# PIC_Uhrfinal.net
KiCad netlist of a schematic drawn in EAGLE
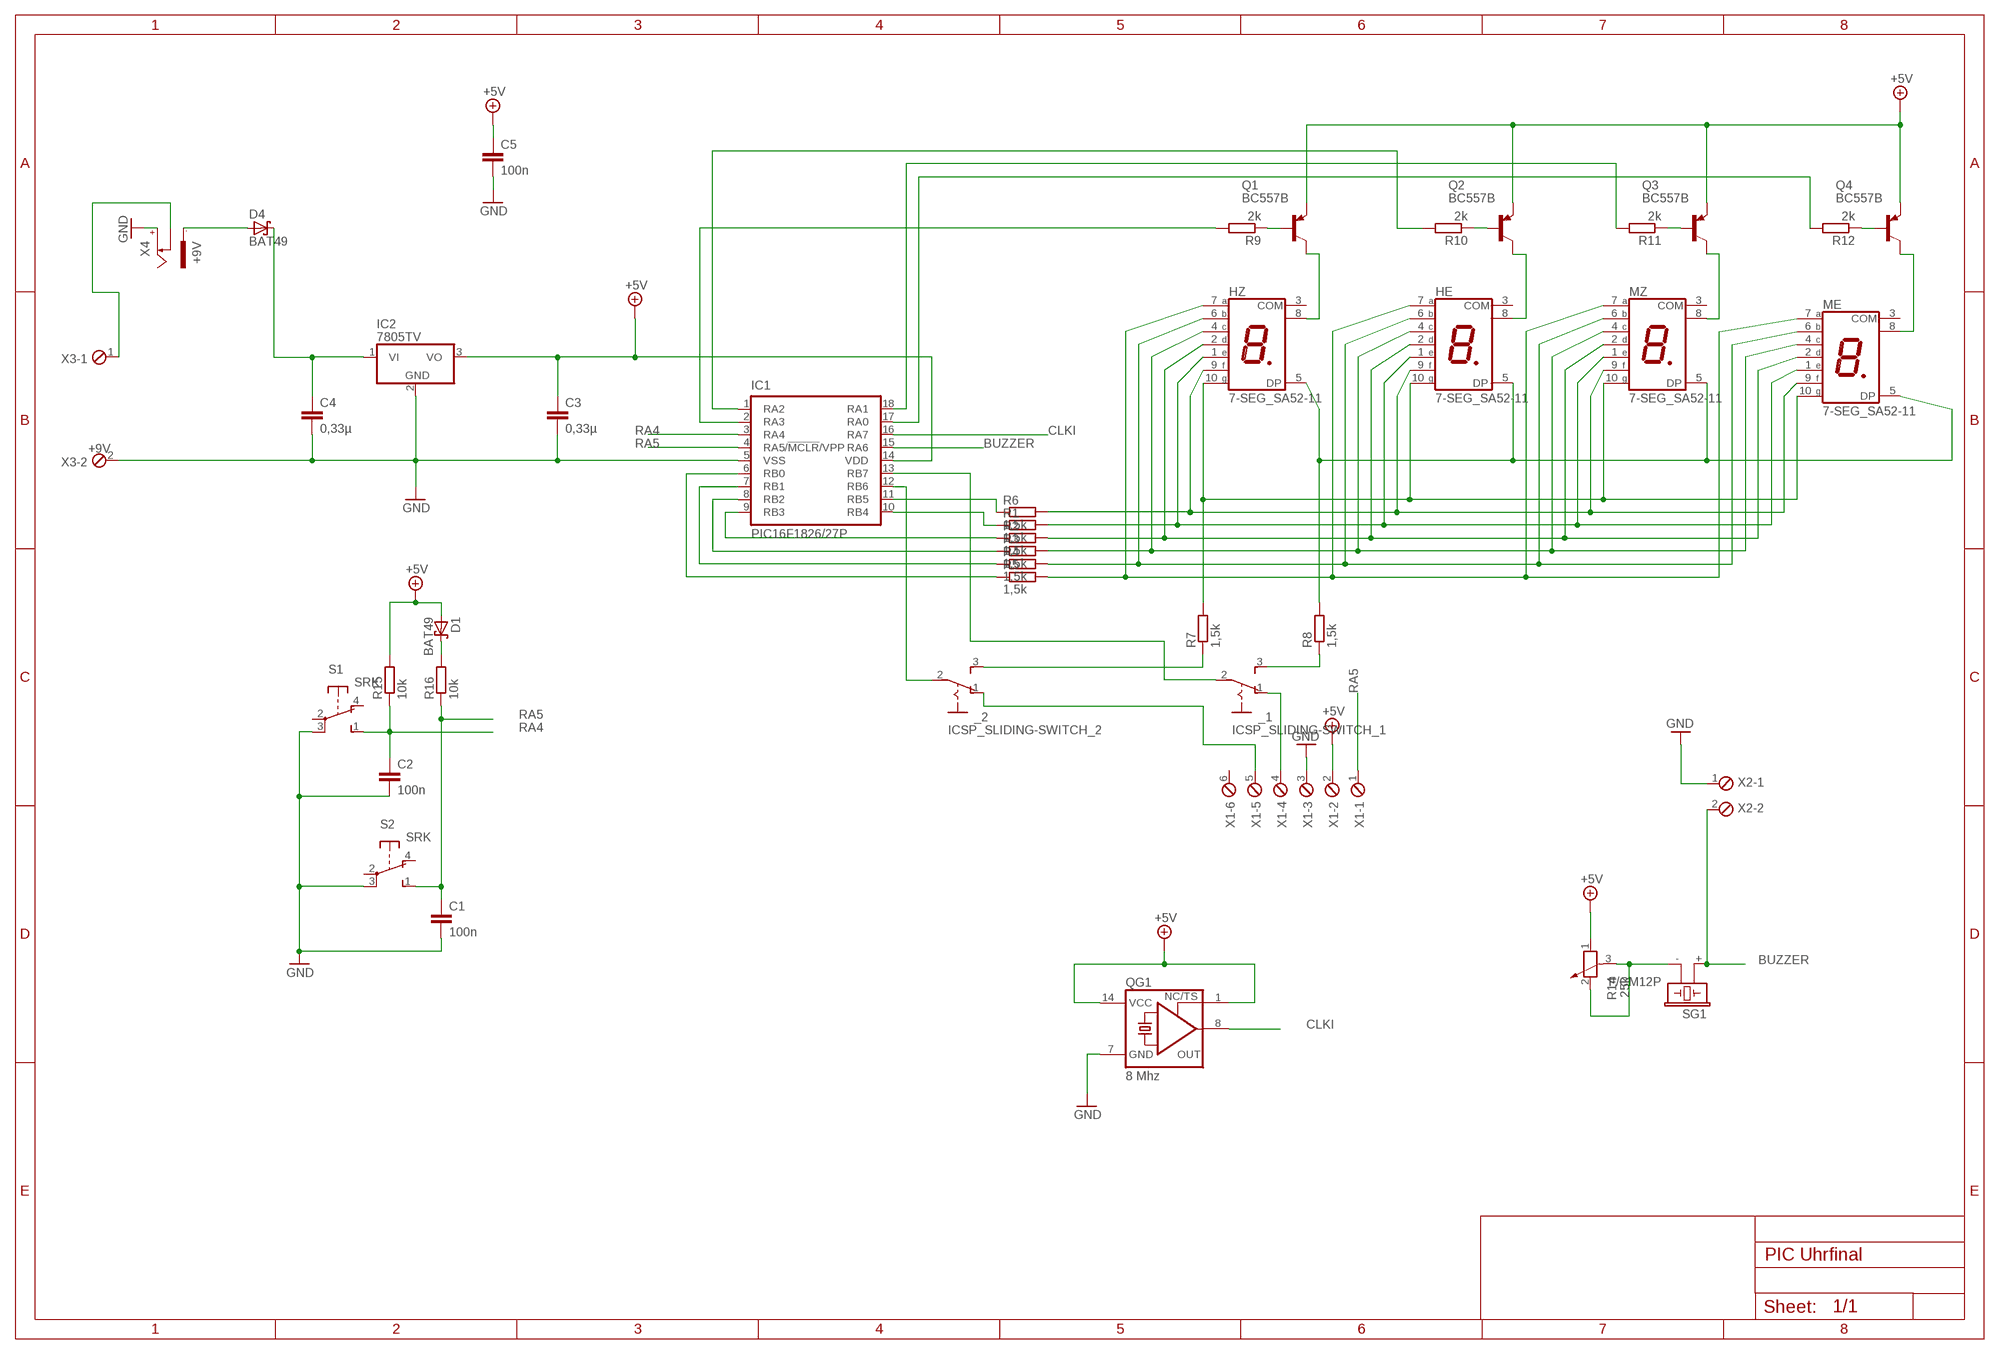
[diagram p0: schematic, sheet 1]

(export (version "E")
  (design (tool "Eeschema 10.0.6"))
  (components
    (comp (ref "C1")
      (value "100n")
      (footprint "eagle-import:C1206")
      (libsource (lib "eagle-import") (part "C-EUC1206"))
    )
    (comp (ref "C2")
      (value "100n")
      (footprint "eagle-import:C1206")
      (libsource (lib "eagle-import") (part "C-EUC1206"))
    )
    (comp (ref "C3")
      (value "0,33µ")
      (footprint "eagle-import:C1206")
      (libsource (lib "eagle-import") (part "C-EUC1206"))
    )
    (comp (ref "C4")
      (value "0,33µ")
      (footprint "eagle-import:C1206")
      (libsource (lib "eagle-import") (part "C-EUC1206"))
    )
    (comp (ref "C5")
      (value "100n")
      (footprint "eagle-import:C1206")
      (libsource (lib "eagle-import") (part "C-EUC1206"))
    )
    (comp (ref "D1")
      (value "BAT49")
      (footprint "eagle-import:DO41-10")
      (libsource (lib "eagle-import") (part "BAT49"))
    )
    (comp (ref "D4")
      (value "BAT49")
      (footprint "eagle-import:DO41-10")
      (libsource (lib "eagle-import") (part "BAT49"))
    )
    (comp (ref "HE")
      (value "7-SEG_SA52-11")
      (footprint "eagle-import:SA52-11")
      (libsource (lib "eagle-import") (part "7-SEG_SA52-11"))
    )
    (comp (ref "HZ")
      (value "7-SEG_SA52-11")
      (footprint "eagle-import:SA52-11")
      (libsource (lib "eagle-import") (part "7-SEG_SA52-11"))
    )
    (comp (ref "IC1")
      (value "PIC16F1826/27P")
      (footprint "eagle-import:DIL18")
      (libsource (lib "eagle-import") (part "PIC16F1826/27P"))
    )
    (comp (ref "IC2")
      (value "7805TV")
      (footprint "eagle-import:TO220V")
      (libsource (lib "eagle-import") (part "78TV05"))
    )
    (comp (ref "ICSP_SLIDING-SWITCH_1")
      (value "_1")
      (footprint "eagle-import:M251")
      (libsource (lib "eagle-import") (part "M251"))
    )
    (comp (ref "ICSP_SLIDING-SWITCH_2")
      (value "_2")
      (footprint "eagle-import:M251")
      (libsource (lib "eagle-import") (part "M251"))
    )
    (comp (ref "ME")
      (value "7-SEG_SA52-11")
      (footprint "eagle-import:SA52-11")
      (libsource (lib "eagle-import") (part "7-SEG_SA52-11"))
    )
    (comp (ref "MZ")
      (value "7-SEG_SA52-11")
      (footprint "eagle-import:SA52-11")
      (libsource (lib "eagle-import") (part "7-SEG_SA52-11"))
    )
    (comp (ref "Q1")
      (value "BC557B")
      (footprint "eagle-import:TO92-EBC")
      (libsource (lib "eagle-import") (part "BC557B"))
    )
    (comp (ref "Q2")
      (value "BC557B")
      (footprint "eagle-import:TO92-EBC")
      (libsource (lib "eagle-import") (part "BC557B"))
    )
    (comp (ref "Q3")
      (value "BC557B")
      (footprint "eagle-import:TO92-EBC")
      (libsource (lib "eagle-import") (part "BC557B"))
    )
    (comp (ref "Q4")
      (value "BC557B")
      (footprint "eagle-import:TO92-EBC")
      (libsource (lib "eagle-import") (part "BC557B"))
    )
    (comp (ref "QG1")
      (value "8 Mhz")
      (footprint "eagle-import:DIL14S")
      (libsource (lib "eagle-import") (part "XO-14"))
    )
    (comp (ref "R1")
      (value "1,5k")
      (footprint "eagle-import:R0805W")
      (libsource (lib "eagle-import") (part "R-EU_R0805W"))
    )
    (comp (ref "R2")
      (value "1,5k")
      (footprint "eagle-import:R0805W")
      (libsource (lib "eagle-import") (part "R-EU_R0805W"))
    )
    (comp (ref "R3")
      (value "1,5k")
      (footprint "eagle-import:R0805W")
      (libsource (lib "eagle-import") (part "R-EU_R0805W"))
    )
    (comp (ref "R4")
      (value "1,5k")
      (footprint "eagle-import:R0805W")
      (libsource (lib "eagle-import") (part "R-EU_R0805W"))
    )
    (comp (ref "R5")
      (value "1,5k")
      (footprint "eagle-import:R0805W")
      (libsource (lib "eagle-import") (part "R-EU_R0805W"))
    )
    (comp (ref "R6")
      (value "1,5k")
      (footprint "eagle-import:R0805W")
      (libsource (lib "eagle-import") (part "R-EU_R0805W"))
    )
    (comp (ref "R7")
      (value "1,5k")
      (footprint "eagle-import:R0805W")
      (libsource (lib "eagle-import") (part "R-EU_R0805W"))
    )
    (comp (ref "R8")
      (value "1,5k")
      (footprint "eagle-import:R0805W")
      (libsource (lib "eagle-import") (part "R-EU_R0805W"))
    )
    (comp (ref "R9")
      (value "2k")
      (footprint "eagle-import:R0805W")
      (libsource (lib "eagle-import") (part "R-EU_R0805W"))
    )
    (comp (ref "R10")
      (value "2k")
      (footprint "eagle-import:R0805W")
      (libsource (lib "eagle-import") (part "R-EU_R0805W"))
    )
    (comp (ref "R11")
      (value "2k")
      (footprint "eagle-import:R0805W")
      (libsource (lib "eagle-import") (part "R-EU_R0805W"))
    )
    (comp (ref "R12")
      (value "2k")
      (footprint "eagle-import:R0805W")
      (libsource (lib "eagle-import") (part "R-EU_R0805W"))
    )
    (comp (ref "R14")
      (value "25k")
      (footprint "eagle-import:PT-10")
      (libsource (lib "eagle-import") (part "POTENTIOMETER_PT-10"))
    )
    (comp (ref "R15")
      (value "10k")
      (footprint "eagle-import:R1206")
      (libsource (lib "eagle-import") (part "R-EU_R1206"))
    )
    (comp (ref "R16")
      (value "10k")
      (footprint "eagle-import:R1206")
      (libsource (lib "eagle-import") (part "R-EU_R1206"))
    )
    (comp (ref "S1")
      (value "SRK")
      (footprint "eagle-import:SRK")
      (libsource (lib "eagle-import") (part "SRK"))
    )
    (comp (ref "S2")
      (value "SRK")
      (footprint "eagle-import:SRK")
      (libsource (lib "eagle-import") (part "SRK"))
    )
    (comp (ref "SG1")
      (value "F/CM12P")
      (footprint "eagle-import:F_CM12P")
      (libsource (lib "eagle-import") (part "F/CM12P"))
    )
    (comp (ref "X1")
      (value "MPT6")
      (footprint "eagle-import:6POL254")
      (libsource (lib "eagle-import") (part "MPT6"))
    )
    (comp (ref "X2")
      (value "MPT2")
      (footprint "eagle-import:2POL254")
      (libsource (lib "eagle-import") (part "MPT2"))
    )
    (comp (ref "X3")
      (value "+9V")
      (footprint "eagle-import:2POL254")
      (libsource (lib "eagle-import") (part "MPT2"))
    )
    (comp (ref "X4")
      (value "+9V")
      (footprint "eagle-import:737992-5")
      (libsource (lib "eagle-import") (part "737992-55"))
    )
  )
  (nets
    (net (code "1") (name "+5V") (class "Default")
      (node (ref "C3") (pin "1") (pinfunction "1_1") (pintype "passive"))
      (node (ref "C5") (pin "1") (pinfunction "1_1") (pintype "passive"))
      (node (ref "D1") (pin "A") (pinfunction "A_A") (pintype "passive"))
      (node (ref "IC1") (pin "14") (pinfunction "VDD_14") (pintype "power_in"))
      (node (ref "IC2") (pin "3") (pinfunction "VO_3") (pintype "passive"))
      (node (ref "Q1") (pin "E") (pinfunction "E_E") (pintype "passive"))
      (node (ref "Q2") (pin "E") (pinfunction "E_E") (pintype "passive"))
      (node (ref "Q3") (pin "E") (pinfunction "E_E") (pintype "passive"))
      (node (ref "Q4") (pin "E") (pinfunction "E_E") (pintype "passive"))
      (node (ref "QG1") (pin "1") (pinfunction "TS_1") (pintype "passive"))
      (node (ref "QG1") (pin "14") (pinfunction "VCC_14") (pintype "power_in"))
      (node (ref "R14") (pin "1") (pinfunction "1_1") (pintype "passive"))
      (node (ref "R15") (pin "2") (pinfunction "2_2") (pintype "passive"))
      (node (ref "X1") (pin "2") (pinfunction "1_2") (pintype "passive"))
    )
    (net (code "2") (name "/BUZZER") (class "Default")
      (node (ref "IC1") (pin "15") (pinfunction "RA6_15") (pintype "bidirectional"))
      (node (ref "SG1") (pin "+") (pinfunction "1_+") (pintype "passive"))
      (node (ref "X2") (pin "2") (pinfunction "1_2") (pintype "passive"))
    )
    (net (code "3") (name "/CLKI") (class "Default")
      (node (ref "IC1") (pin "16") (pinfunction "RA7_16") (pintype "bidirectional"))
      (node (ref "QG1") (pin "8") (pinfunction "OUT_8") (pintype "output"))
    )
    (net (code "4") (name "/RA4") (class "Default")
      (node (ref "C2") (pin "1") (pinfunction "1_1") (pintype "passive"))
      (node (ref "IC1") (pin "3") (pinfunction "RA4_3") (pintype "bidirectional"))
      (node (ref "R15") (pin "1") (pinfunction "1_1") (pintype "passive"))
      (node (ref "S1") (pin "1") (pinfunction "S_1") (pintype "passive"))
    )
    (net (code "5") (name "/RA5") (class "Default")
      (node (ref "C1") (pin "1") (pinfunction "1_1") (pintype "passive"))
      (node (ref "IC1") (pin "4") (pinfunction "RA5/~{MCLR}/VPP_4") (pintype "bidirectional"))
      (node (ref "R16") (pin "1") (pinfunction "1_1") (pintype "passive"))
      (node (ref "S2") (pin "1") (pinfunction "S_1") (pintype "passive"))
      (node (ref "X1") (pin "1") (pinfunction "1_1") (pintype "passive"))
    )
    (net (code "6") (name "GND") (class "Default")
      (node (ref "C1") (pin "2") (pinfunction "2_2") (pintype "passive"))
      (node (ref "C2") (pin "2") (pinfunction "2_2") (pintype "passive"))
      (node (ref "C3") (pin "2") (pinfunction "2_2") (pintype "passive"))
      (node (ref "C4") (pin "2") (pinfunction "2_2") (pintype "passive"))
      (node (ref "C5") (pin "2") (pinfunction "2_2") (pintype "passive"))
      (node (ref "IC1") (pin "5") (pinfunction "VSS_5") (pintype "power_in"))
      (node (ref "IC2") (pin "2") (pinfunction "GND_2") (pintype "passive"))
      (node (ref "QG1") (pin "7") (pinfunction "GND_7") (pintype "power_in"))
      (node (ref "S1") (pin "3") (pinfunction "P_3") (pintype "passive"))
      (node (ref "S2") (pin "3") (pinfunction "P_3") (pintype "passive"))
      (node (ref "X1") (pin "3") (pinfunction "1_3") (pintype "passive"))
      (node (ref "X2") (pin "1") (pinfunction "1_1") (pintype "passive"))
      (node (ref "X3") (pin "2") (pinfunction "1_2") (pintype "passive"))
      (node (ref "X4") (pin "+") (pinfunction "+_+") (pintype "passive"))
    )
    (net (code "7") (name "Net-(D1-PadC)") (class "Default")
      (node (ref "D1") (pin "C") (pinfunction "C_C") (pintype "passive"))
      (node (ref "R16") (pin "2") (pinfunction "2_2") (pintype "passive"))
    )
    (net (code "8") (name "Net-(D4-PadA)") (class "Default")
      (node (ref "D4") (pin "A") (pinfunction "A_A") (pintype "passive"))
      (node (ref "X4") (pin "-1") (pinfunction "-1_-1") (pintype "passive"))
    )
    (net (code "9") (name "Net-(HE-A)") (class "Default")
      (node (ref "HE") (pin "7") (pinfunction "A_7") (pintype "passive"))
      (node (ref "HZ") (pin "7") (pinfunction "A_7") (pintype "passive"))
      (node (ref "ME") (pin "7") (pinfunction "A_7") (pintype "passive"))
      (node (ref "MZ") (pin "7") (pinfunction "A_7") (pintype "passive"))
      (node (ref "R5") (pin "2") (pinfunction "2_2") (pintype "passive"))
    )
    (net (code "10") (name "Net-(HE-B)") (class "Default")
      (node (ref "HE") (pin "6") (pinfunction "B_6") (pintype "passive"))
      (node (ref "HZ") (pin "6") (pinfunction "B_6") (pintype "passive"))
      (node (ref "ME") (pin "6") (pinfunction "B_6") (pintype "passive"))
      (node (ref "MZ") (pin "6") (pinfunction "B_6") (pintype "passive"))
      (node (ref "R4") (pin "2") (pinfunction "2_2") (pintype "passive"))
    )
    (net (code "11") (name "Net-(HE-C)") (class "Default")
      (node (ref "HE") (pin "4") (pinfunction "C_4") (pintype "passive"))
      (node (ref "HZ") (pin "4") (pinfunction "C_4") (pintype "passive"))
      (node (ref "ME") (pin "4") (pinfunction "C_4") (pintype "passive"))
      (node (ref "MZ") (pin "4") (pinfunction "C_4") (pintype "passive"))
      (node (ref "R3") (pin "2") (pinfunction "2_2") (pintype "passive"))
    )
    (net (code "12") (name "Net-(HE-COM-Pad8)") (class "Default")
      (node (ref "HE") (pin "8") (pinfunction "COM_8") (pintype "passive"))
      (node (ref "Q2") (pin "C") (pinfunction "C_C") (pintype "passive"))
    )
    (net (code "13") (name "Net-(HE-D)") (class "Default")
      (node (ref "HE") (pin "2") (pinfunction "D_2") (pintype "passive"))
      (node (ref "HZ") (pin "2") (pinfunction "D_2") (pintype "passive"))
      (node (ref "ME") (pin "2") (pinfunction "D_2") (pintype "passive"))
      (node (ref "MZ") (pin "2") (pinfunction "D_2") (pintype "passive"))
      (node (ref "R2") (pin "2") (pinfunction "2_2") (pintype "passive"))
    )
    (net (code "14") (name "Net-(HE-DP)") (class "Default")
      (node (ref "HE") (pin "5") (pinfunction "DP_5") (pintype "passive"))
      (node (ref "HZ") (pin "5") (pinfunction "DP_5") (pintype "passive"))
      (node (ref "ME") (pin "5") (pinfunction "DP_5") (pintype "passive"))
      (node (ref "MZ") (pin "5") (pinfunction "DP_5") (pintype "passive"))
      (node (ref "R8") (pin "2") (pinfunction "2_2") (pintype "passive"))
    )
    (net (code "15") (name "Net-(HE-E)") (class "Default")
      (node (ref "HE") (pin "1") (pinfunction "E_1") (pintype "passive"))
      (node (ref "HZ") (pin "1") (pinfunction "E_1") (pintype "passive"))
      (node (ref "ME") (pin "1") (pinfunction "E_1") (pintype "passive"))
      (node (ref "MZ") (pin "1") (pinfunction "E_1") (pintype "passive"))
      (node (ref "R1") (pin "2") (pinfunction "2_2") (pintype "passive"))
    )
    (net (code "16") (name "Net-(HE-F)") (class "Default")
      (node (ref "HE") (pin "9") (pinfunction "F_9") (pintype "passive"))
      (node (ref "HZ") (pin "9") (pinfunction "F_9") (pintype "passive"))
      (node (ref "ME") (pin "9") (pinfunction "F_9") (pintype "passive"))
      (node (ref "MZ") (pin "9") (pinfunction "F_9") (pintype "passive"))
      (node (ref "R6") (pin "2") (pinfunction "2_2") (pintype "passive"))
    )
    (net (code "17") (name "Net-(HE-G)") (class "Default")
      (node (ref "HE") (pin "10") (pinfunction "G_10") (pintype "passive"))
      (node (ref "HZ") (pin "10") (pinfunction "G_10") (pintype "passive"))
      (node (ref "ME") (pin "10") (pinfunction "G_10") (pintype "passive"))
      (node (ref "MZ") (pin "10") (pinfunction "G_10") (pintype "passive"))
      (node (ref "R7") (pin "2") (pinfunction "2_2") (pintype "passive"))
    )
    (net (code "18") (name "Net-(HZ-COM-Pad8)") (class "Default")
      (node (ref "HZ") (pin "8") (pinfunction "COM_8") (pintype "passive"))
      (node (ref "Q1") (pin "C") (pinfunction "C_C") (pintype "passive"))
    )
    (net (code "19") (name "Net-(IC1-RA0)") (class "Default")
      (node (ref "IC1") (pin "17") (pinfunction "RA0_17") (pintype "bidirectional"))
      (node (ref "R12") (pin "2") (pinfunction "2_2") (pintype "passive"))
    )
    (net (code "20") (name "Net-(IC1-RA1)") (class "Default")
      (node (ref "IC1") (pin "18") (pinfunction "RA1_18") (pintype "bidirectional"))
      (node (ref "R11") (pin "2") (pinfunction "2_2") (pintype "passive"))
    )
    (net (code "21") (name "Net-(IC1-RA2)") (class "Default")
      (node (ref "IC1") (pin "1") (pinfunction "RA2_1") (pintype "bidirectional"))
      (node (ref "R10") (pin "2") (pinfunction "2_2") (pintype "passive"))
    )
    (net (code "22") (name "Net-(IC1-RA3)") (class "Default")
      (node (ref "IC1") (pin "2") (pinfunction "RA3_2") (pintype "bidirectional"))
      (node (ref "R9") (pin "2") (pinfunction "2_2") (pintype "passive"))
    )
    (net (code "23") (name "Net-(IC1-RB0)") (class "Default")
      (node (ref "IC1") (pin "6") (pinfunction "RB0_6") (pintype "bidirectional"))
      (node (ref "R5") (pin "1") (pinfunction "1_1") (pintype "passive"))
    )
    (net (code "24") (name "Net-(IC1-RB1)") (class "Default")
      (node (ref "IC1") (pin "7") (pinfunction "RB1_7") (pintype "bidirectional"))
      (node (ref "R4") (pin "1") (pinfunction "1_1") (pintype "passive"))
    )
    (net (code "25") (name "Net-(IC1-RB2)") (class "Default")
      (node (ref "IC1") (pin "8") (pinfunction "RB2_8") (pintype "bidirectional"))
      (node (ref "R3") (pin "1") (pinfunction "1_1") (pintype "passive"))
    )
    (net (code "26") (name "Net-(IC1-RB3)") (class "Default")
      (node (ref "IC1") (pin "9") (pinfunction "RB3_9") (pintype "bidirectional"))
      (node (ref "R2") (pin "1") (pinfunction "1_1") (pintype "passive"))
    )
    (net (code "27") (name "Net-(IC1-RB4)") (class "Default")
      (node (ref "IC1") (pin "10") (pinfunction "RB4_10") (pintype "bidirectional"))
      (node (ref "R1") (pin "1") (pinfunction "1_1") (pintype "passive"))
    )
    (net (code "28") (name "Net-(IC1-RB5)") (class "Default")
      (node (ref "IC1") (pin "11") (pinfunction "RB5_11") (pintype "bidirectional"))
      (node (ref "R6") (pin "1") (pinfunction "1_1") (pintype "passive"))
    )
    (net (code "29") (name "Net-(IC1-RB6)") (class "Default")
      (node (ref "IC1") (pin "12") (pinfunction "RB6_12") (pintype "bidirectional"))
      (node (ref "ICSP_SLIDING-SWITCH_2") (pin "2") (pinfunction "P_2") (pintype "passive"))
    )
    (net (code "30") (name "Net-(IC1-RB7)") (class "Default")
      (node (ref "IC1") (pin "13") (pinfunction "RB7_13") (pintype "bidirectional"))
      (node (ref "ICSP_SLIDING-SWITCH_1") (pin "2") (pinfunction "P_2") (pintype "passive"))
    )
    (net (code "31") (name "Net-(IC2-VI)") (class "Default")
      (node (ref "C4") (pin "1") (pinfunction "1_1") (pintype "passive"))
      (node (ref "D4") (pin "C") (pinfunction "C_C") (pintype "passive"))
      (node (ref "IC2") (pin "1") (pinfunction "VI_1") (pintype "input"))
    )
    (net (code "32") (name "Net-(ICSP_SLIDING-SWITCH_1-O)") (class "Default")
      (node (ref "ICSP_SLIDING-SWITCH_1") (pin "1") (pinfunction "O_1") (pintype "passive"))
      (node (ref "X1") (pin "4") (pinfunction "1_4") (pintype "passive"))
    )
    (net (code "33") (name "Net-(ICSP_SLIDING-SWITCH_1-S)") (class "Default")
      (node (ref "ICSP_SLIDING-SWITCH_1") (pin "3") (pinfunction "S_3") (pintype "passive"))
      (node (ref "R8") (pin "1") (pinfunction "1_1") (pintype "passive"))
    )
    (net (code "34") (name "Net-(ICSP_SLIDING-SWITCH_2-O)") (class "Default")
      (node (ref "ICSP_SLIDING-SWITCH_2") (pin "1") (pinfunction "O_1") (pintype "passive"))
      (node (ref "X1") (pin "5") (pinfunction "1_5") (pintype "passive"))
    )
    (net (code "35") (name "Net-(ICSP_SLIDING-SWITCH_2-S)") (class "Default")
      (node (ref "ICSP_SLIDING-SWITCH_2") (pin "3") (pinfunction "S_3") (pintype "passive"))
      (node (ref "R7") (pin "1") (pinfunction "1_1") (pintype "passive"))
    )
    (net (code "36") (name "Net-(ME-COM-Pad8)") (class "Default")
      (node (ref "ME") (pin "8") (pinfunction "COM_8") (pintype "passive"))
      (node (ref "Q4") (pin "C") (pinfunction "C_C") (pintype "passive"))
    )
    (net (code "37") (name "Net-(MZ-COM-Pad8)") (class "Default")
      (node (ref "MZ") (pin "8") (pinfunction "COM_8") (pintype "passive"))
      (node (ref "Q3") (pin "C") (pinfunction "C_C") (pintype "passive"))
    )
    (net (code "38") (name "Net-(Q1-PadB)") (class "Default")
      (node (ref "Q1") (pin "B") (pinfunction "B_B") (pintype "passive"))
      (node (ref "R9") (pin "1") (pinfunction "1_1") (pintype "passive"))
    )
    (net (code "39") (name "Net-(Q2-PadB)") (class "Default")
      (node (ref "Q2") (pin "B") (pinfunction "B_B") (pintype "passive"))
      (node (ref "R10") (pin "1") (pinfunction "1_1") (pintype "passive"))
    )
    (net (code "40") (name "Net-(Q3-PadB)") (class "Default")
      (node (ref "Q3") (pin "B") (pinfunction "B_B") (pintype "passive"))
      (node (ref "R11") (pin "1") (pinfunction "1_1") (pintype "passive"))
    )
    (net (code "41") (name "Net-(Q4-PadB)") (class "Default")
      (node (ref "Q4") (pin "B") (pinfunction "B_B") (pintype "passive"))
      (node (ref "R12") (pin "1") (pinfunction "1_1") (pintype "passive"))
    )
    (net (code "42") (name "Net-(SG1-2)") (class "Default")
      (node (ref "R14") (pin "2") (pinfunction "2_2") (pintype "passive"))
      (node (ref "R14") (pin "3") (pinfunction "3_3") (pintype "passive"))
      (node (ref "SG1") (pin "-") (pinfunction "2_-") (pintype "passive"))
    )
    (net (code "43") (name "Net-(X3-Pad1)") (class "Default")
      (node (ref "X3") (pin "1") (pinfunction "1_1") (pintype "passive"))
      (node (ref "X4") (pin "K") (pinfunction "K_K") (pintype "passive"))
    )
    (net (code "44") (name "unconnected-(HE-COM-Pad3)") (class "Default")
      (node (ref "HE") (pin "3") (pinfunction "COM_3") (pintype "passive"))
    )
    (net (code "45") (name "unconnected-(HZ-COM-Pad3)") (class "Default")
      (node (ref "HZ") (pin "3") (pinfunction "COM_3") (pintype "passive"))
    )
    (net (code "46") (name "unconnected-(ME-COM-Pad3)") (class "Default")
      (node (ref "ME") (pin "3") (pinfunction "COM_3") (pintype "passive"))
    )
    (net (code "47") (name "unconnected-(MZ-COM-Pad3)") (class "Default")
      (node (ref "MZ") (pin "3") (pinfunction "COM_3") (pintype "passive"))
    )
    (net (code "48") (name "unconnected-(S1-O-Pad4)") (class "Default")
      (node (ref "S1") (pin "4") (pinfunction "O_4") (pintype "passive"))
    )
    (net (code "49") (name "unconnected-(S1-P-Pad2)") (class "Default")
      (node (ref "S1") (pin "2") (pinfunction "P_2") (pintype "passive"))
    )
    (net (code "50") (name "unconnected-(S2-O-Pad4)") (class "Default")
      (node (ref "S2") (pin "4") (pinfunction "O_4") (pintype "passive"))
    )
    (net (code "51") (name "unconnected-(S2-P-Pad2)") (class "Default")
      (node (ref "S2") (pin "2") (pinfunction "P_2") (pintype "passive"))
    )
    (net (code "52") (name "unconnected-(X1F-1-Pad6)") (class "Default")
      (node (ref "X1") (pin "6") (pinfunction "1_6") (pintype "passive"))
    )
    (net (code "53") (name "unconnected-(X4-Pad-2)") (class "Default")
      (node (ref "X4") (pin "-2") (pinfunction "-2_-2") (pintype "passive"))
    )
  )
)
